# C-04_CPU_PERI1.net
KiCad netlist of a schematic drawn in Altium Designer
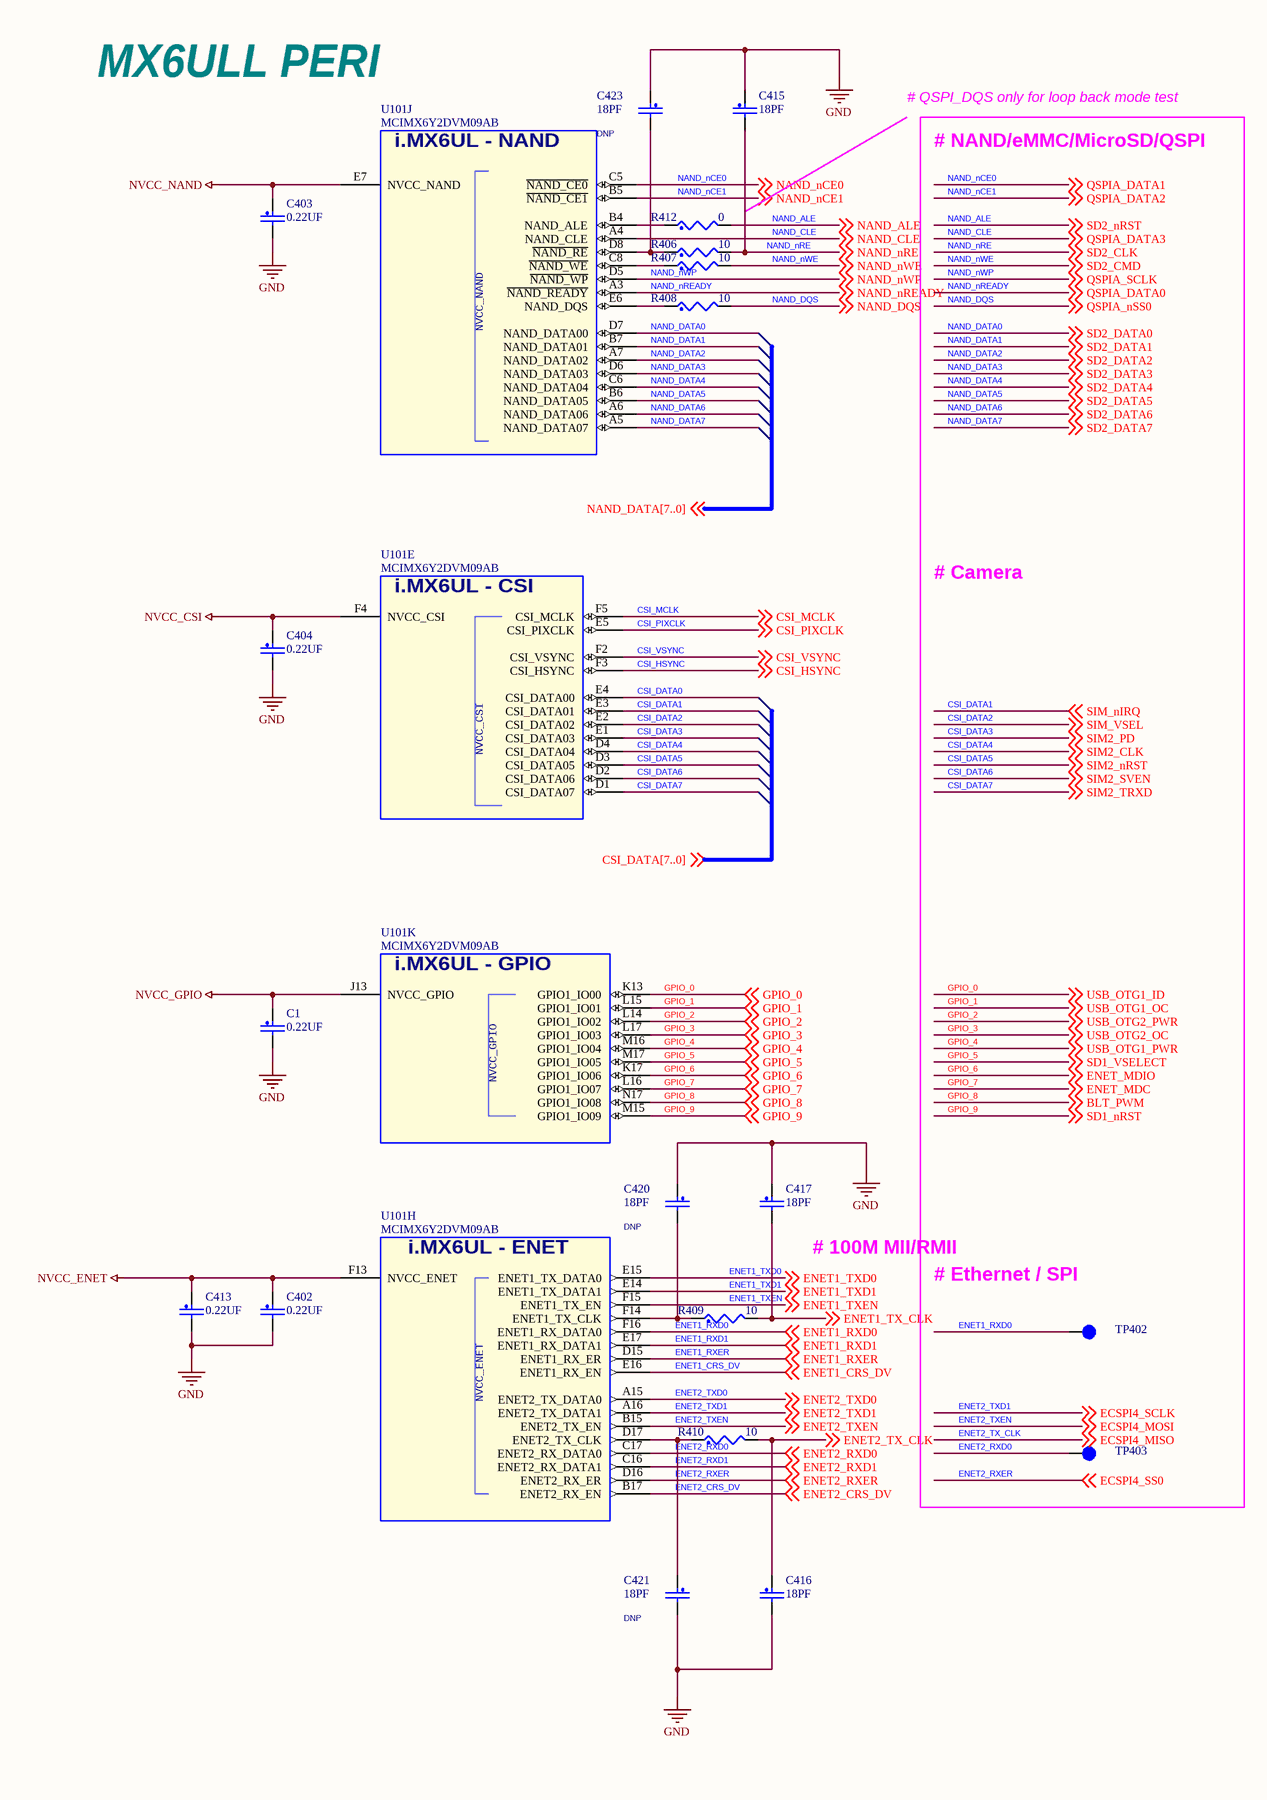
[diagram p0: C-04 CPU PERI1.SchDoc, left]
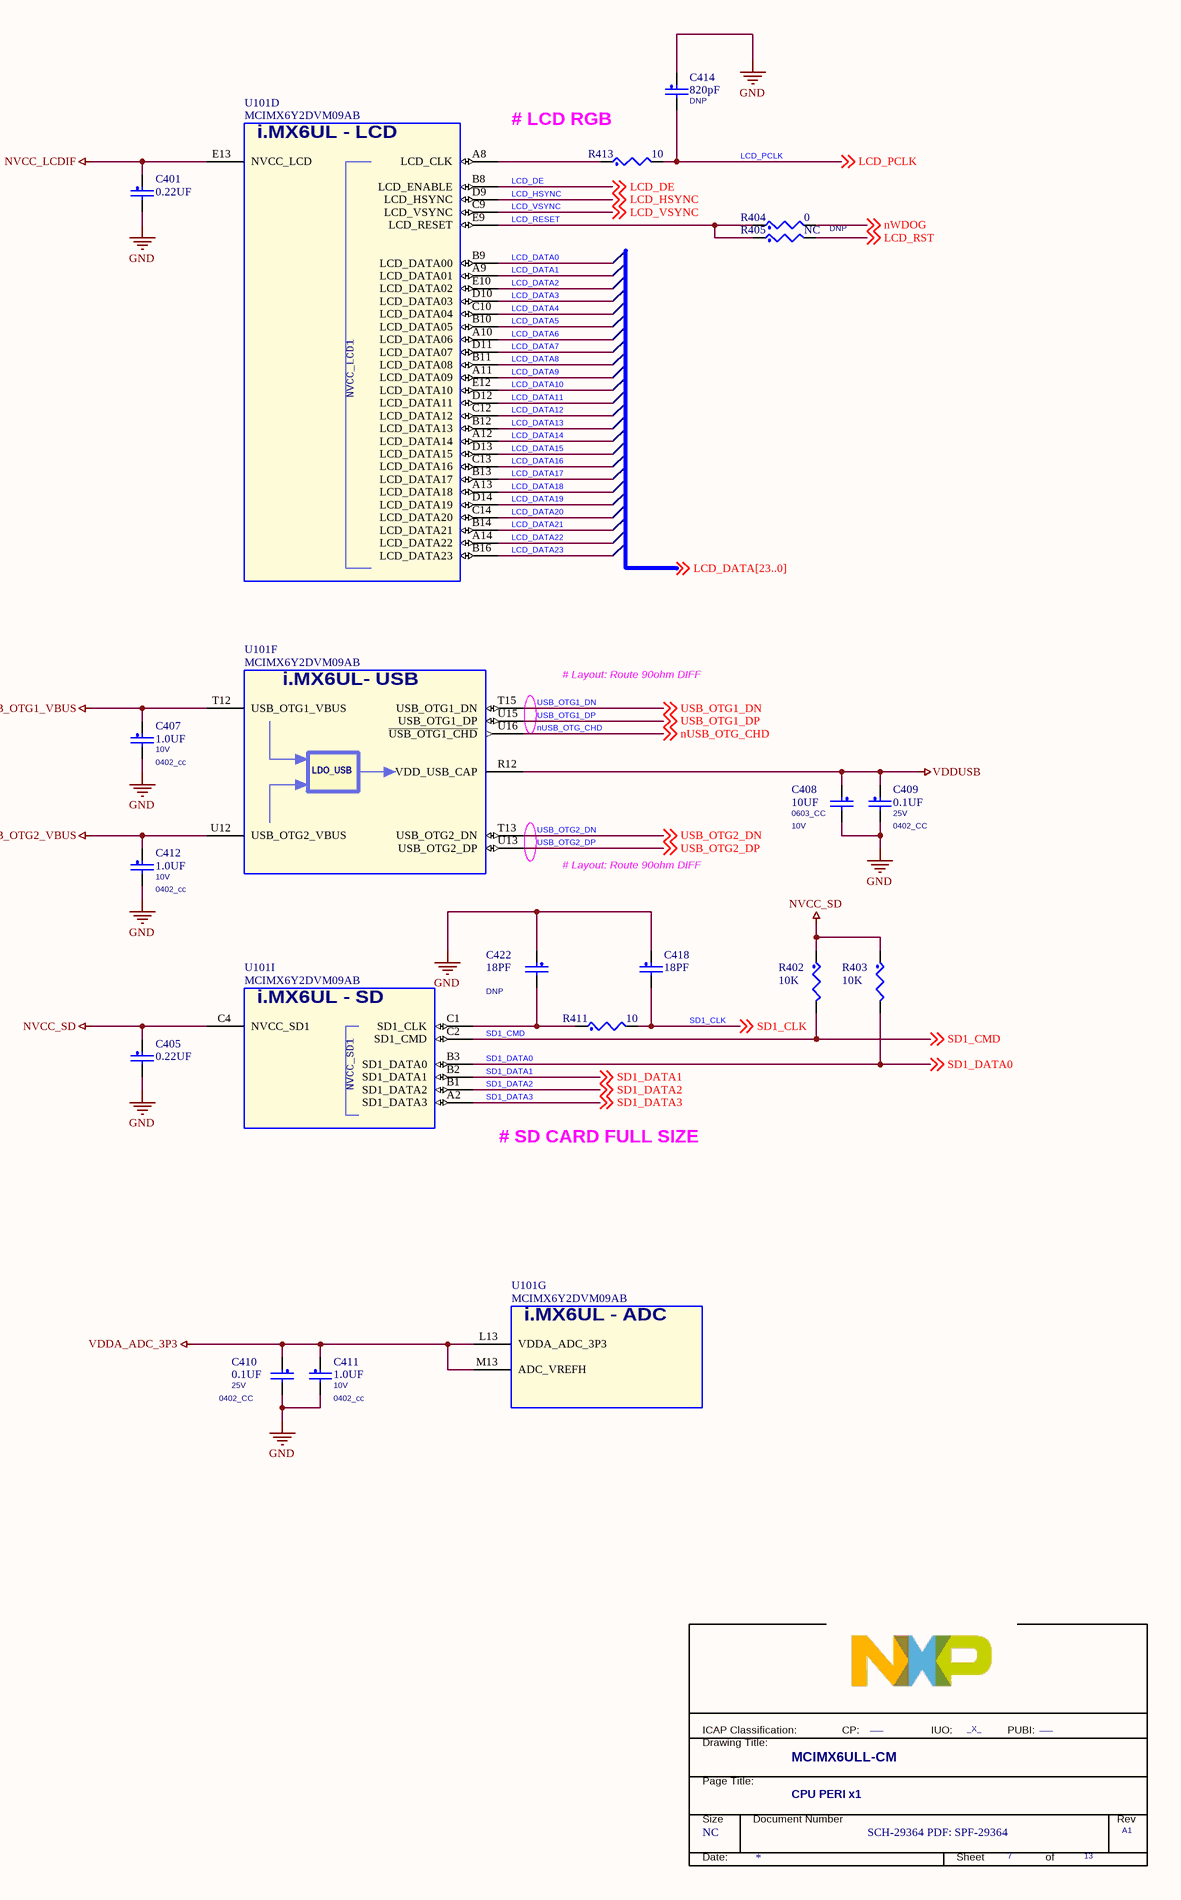
[diagram p1: C-04 CPU PERI1.SchDoc, right]

(export (version "E")
  (design (tool "Eeschema 10.0.6"))
  (components
    (comp (ref "*")
      (value "TitleBlock_FS")
      (fields
        (field (name "PAGETITLE") "CPU PERI x1")
        (field (name "PAGE COUNT") "13")
        (field (name "PAGE NUMBER") "7")
        (field (name "PAGE SIZE") "NC")
        (field (name "TITLE") "MCIMX6ULL-CM")
        (field (name "REVCODE") "A1")
        (field (name "DOC") "SCH-29364 PDF: SPF-29364")
        (field (name "FCP") "___")
        (field (name "PUBI") "___")
        (field (name "FIUO") "_X_")
      )
      (libsource (lib "*") (part "TitleBlock_FS"))
    )
    (comp (ref "C1")
      (value "0.22UF")
      (footprint "0402T_C")
      (description "CAP CER 0.22UF 10V 10% X5R 0402")
      (fields (field (name "VOLTAGE") "10V") (field (name "TOLERANCE") "10%"))
      (libsource (lib "*") (part "CAP_NP"))
    )
    (comp (ref "C401")
      (value "0.22UF")
      (footprint "0402T_C")
      (description "CAP CER 0.22UF 10V 10% X5R 0402")
      (fields (field (name "VOLTAGE") "10V") (field (name "TOLERANCE") "10%"))
      (libsource (lib "*") (part "CAP_NP"))
    )
    (comp (ref "C402")
      (value "0.22UF")
      (footprint "0402T_C")
      (description "CAP CER 0.22UF 10V 10% X5R 0402")
      (fields (field (name "VOLTAGE") "10V") (field (name "TOLERANCE") "10%"))
      (libsource (lib "*") (part "CAP_NP"))
    )
    (comp (ref "C403")
      (value "0.22UF")
      (footprint "0402T_C")
      (description "CAP CER 0.22UF 10V 10% X5R 0402")
      (fields (field (name "VOLTAGE") "10V") (field (name "TOLERANCE") "10%"))
      (libsource (lib "*") (part "CAP_NP"))
    )
    (comp (ref "C404")
      (value "0.22UF")
      (footprint "0402T_C")
      (description "CAP CER 0.22UF 10V 10% X5R 0402")
      (fields (field (name "TOLERANCE") "10%") (field (name "VOLTAGE") "10V"))
      (libsource (lib "*") (part "CAP_NP"))
    )
    (comp (ref "C405")
      (value "0.22UF")
      (footprint "0402T_C")
      (description "CAP CER 0.22UF 10V 10% X5R 0402")
      (fields (field (name "TOLERANCE") "10%") (field (name "VOLTAGE") "10V"))
      (libsource (lib "*") (part "CAP_NP"))
    )
    (comp (ref "C407")
      (value "1.0UF")
      (footprint "0402T_C")
      (description "CAP CER 1.0UF 10V 10% X5R 0402")
      (fields (field (name "VOLTAGE") "10V") (field (name "PCB FOOTPRINT") "0402_cc"))
      (libsource (lib "*") (part "CAP_NP"))
    )
    (comp (ref "C408")
      (value "10UF")
      (footprint "0402T_C")
      (description "CAP CER 10UF 10V 20% X5R 0603")
      (fields (field (name "VOLTAGE") "10V") (field (name "PCB FOOTPRINT") "0603_CC"))
      (libsource (lib "*") (part "CAP_NP"))
    )
    (comp (ref "C409")
      (value "0.1UF")
      (footprint "0402T_C")
      (description "CAP CER 0.1UF 25V 10% X5R 0402")
      (fields
        (field (name "VOLTAGE") "25V")
        (field (name "TOLERANCE") "10%")
        (field (name "PCB FOOTPRINT") "0402_CC")
      )
      (libsource (lib "*") (part "CAP_NP"))
    )
    (comp (ref "C410")
      (value "0.1UF")
      (footprint "0402T_C")
      (description "CAP CER 0.1UF 25V 10% X5R 0402")
      (fields
        (field (name "TOLERANCE") "10%")
        (field (name "VOLTAGE") "25V")
        (field (name "PCB FOOTPRINT") "0402_CC")
      )
      (libsource (lib "*") (part "CAP_NP"))
    )
    (comp (ref "C411")
      (value "1.0UF")
      (footprint "0402T_C")
      (description "CAP CER 1.0UF 10V 10% X5R 0402")
      (fields (field (name "VOLTAGE") "10V") (field (name "PCB FOOTPRINT") "0402_cc"))
      (libsource (lib "*") (part "CAP_NP"))
    )
    (comp (ref "C412")
      (value "1.0UF")
      (footprint "0402T_C")
      (description "CAP CER 1.0UF 10V 10% X5R 0402")
      (fields (field (name "VOLTAGE") "10V") (field (name "PCB FOOTPRINT") "0402_cc"))
      (libsource (lib "*") (part "CAP_NP"))
    )
    (comp (ref "C413")
      (value "0.22UF")
      (footprint "0402T_C")
      (description "CAP CER 0.22UF 10V 10% X5R 0402")
      (fields (field (name "VOLTAGE") "10V") (field (name "TOLERANCE") "10%"))
      (libsource (lib "*") (part "CAP_NP"))
    )
    (comp (ref "C414")
      (value "820pF")
      (footprint "0402T_C")
      (description "CAP CER 820PF 50V 5% X7R 0402")
      (fields (field (name "ASSY_OPT") "DNP") (field (name "TOLERANCE") "5%") (field (name "VOLTAGE") "50 V"))
      (libsource (lib "*") (part "CAP_NP"))
    )
    (comp (ref "C415")
      (value "18PF")
      (footprint "0402T_C")
      (description "CAP CER 18PF 50V 1% C0G 0402")
      (fields (field (name "VOLTAGE") "50V") (field (name "TOLERANCE") "1%"))
      (libsource (lib "*") (part "CAP_NP"))
    )
    (comp (ref "C416")
      (value "18PF")
      (footprint "0402T_C")
      (description "CAP CER 18PF 50V 1% C0G 0402")
      (fields (field (name "VOLTAGE") "50V") (field (name "TOLERANCE") "1%"))
      (libsource (lib "*") (part "CAP_NP"))
    )
    (comp (ref "C417")
      (value "18PF")
      (footprint "0402T_C")
      (description "CAP CER 18PF 50V 1% C0G 0402")
      (fields (field (name "VOLTAGE") "50V") (field (name "TOLERANCE") "1%"))
      (libsource (lib "*") (part "CAP_NP"))
    )
    (comp (ref "C418")
      (value "18PF")
      (footprint "0402T_C")
      (description "CAP CER 18PF 50V 1% C0G 0402")
      (fields (field (name "VOLTAGE") "50V") (field (name "TOLERANCE") "1%"))
      (libsource (lib "*") (part "CAP_NP"))
    )
    (comp (ref "C420")
      (value "18PF")
      (footprint "0402T_C")
      (description "CAP CER 18PF 50V 1% C0G 0402")
      (fields (field (name "ASSY_OPT") "DNP") (field (name "VOLTAGE") "50V") (field (name "TOLERANCE") "1%"))
      (libsource (lib "*") (part "CAP_NP"))
    )
    (comp (ref "C421")
      (value "18PF")
      (footprint "0402T_C")
      (description "CAP CER 18PF 50V 1% C0G 0402")
      (fields (field (name "ASSY_OPT") "DNP") (field (name "VOLTAGE") "50V") (field (name "TOLERANCE") "1%"))
      (libsource (lib "*") (part "CAP_NP"))
    )
    (comp (ref "C422")
      (value "18PF")
      (footprint "0402T_C")
      (description "CAP CER 18PF 50V 1% C0G 0402")
      (fields (field (name "ASSY_OPT") "DNP") (field (name "VOLTAGE") "50V") (field (name "TOLERANCE") "1%"))
      (libsource (lib "*") (part "CAP_NP"))
    )
    (comp (ref "C423")
      (value "18PF")
      (footprint "0402T_C")
      (description "CAP CER 18PF 50V 1% C0G 0402")
      (fields (field (name "ASSY_OPT") "DNP") (field (name "VOLTAGE") "50V") (field (name "TOLERANCE") "1%"))
      (libsource (lib "*") (part "CAP_NP"))
    )
    (comp (ref "R402")
      (value "10K")
      (footprint "0402T_C")
      (description "RES MF 10K 1/16W 5% 0402")
      (fields (field (name "TOLERANCE") "5%"))
      (libsource (lib "*") (part "RES"))
    )
    (comp (ref "R403")
      (value "10K")
      (footprint "0402T_C")
      (description "RES MF 10K 1/16W 5% 0402")
      (fields (field (name "TOLERANCE") "5%"))
      (libsource (lib "*") (part "RES"))
    )
    (comp (ref "R404")
      (value "0")
      (footprint "0603_CC")
      (description "RES MF ZERO OHM 1/16W 5% 0402")
      (fields (field (name "TOLERANCE") "5%"))
      (libsource (lib "*") (part "RES"))
    )
    (comp (ref "R405")
      (value "NC")
      (footprint "0402T_C")
      (description "RES MF ZERO OHM 1/16W 5% 0402")
      (fields (field (name "ASSY_OPT") "DNP") (field (name "TOLERANCE") "5%"))
      (libsource (lib "*") (part "RES"))
    )
    (comp (ref "R406")
      (value "10")
      (footprint "0402T_C")
      (description "RES MF 10 OHM 1/16W 5% 0402")
      (fields (field (name "TOLERANCE") "5%"))
      (libsource (lib "*") (part "RES"))
    )
    (comp (ref "R407")
      (value "10")
      (footprint "0402T_C")
      (description "RES MF 10 OHM 1/16W 5% 0402")
      (fields (field (name "TOLERANCE") "5%"))
      (libsource (lib "*") (part "RES"))
    )
    (comp (ref "R408")
      (value "10")
      (footprint "0402T_C")
      (description "RES MF 10 OHM 1/16W 5% 0402")
      (fields (field (name "TOLERANCE") "5%"))
      (libsource (lib "*") (part "RES"))
    )
    (comp (ref "R409")
      (value "10")
      (footprint "0402T_C")
      (description "RES MF 10 OHM 1/16W 5% 0402")
      (fields (field (name "TOLERANCE") "5%"))
      (libsource (lib "*") (part "RES"))
    )
    (comp (ref "R410")
      (value "10")
      (footprint "0402T_C")
      (description "RES MF 10 OHM 1/16W 5% 0402")
      (fields (field (name "TOLERANCE") "5%"))
      (libsource (lib "*") (part "RES"))
    )
    (comp (ref "R411")
      (value "10")
      (footprint "0402T_C")
      (description "RES MF 10 OHM 1/16W 5% 0402")
      (fields (field (name "TOLERANCE") "5%"))
      (libsource (lib "*") (part "RES"))
    )
    (comp (ref "R412")
      (value "0")
      (footprint "0402T_C")
      (description "RES MF ZERO OHM 1/16W 5% 0402")
      (fields (field (name "TOLERANCE") "5%"))
      (libsource (lib "*") (part "RES"))
    )
    (comp (ref "R413")
      (value "10")
      (footprint "0402T_C")
      (description "RES MF 10 OHM 1/16W 5% 0402")
      (fields (field (name "TOLERANCE") "5%"))
      (libsource (lib "*") (part "RES"))
    )
    (comp (ref "TP402")
      (value "TPAD_015")
      (footprint "TPAD_015")
      (description "TEST POINT PAD 15MIL DIA SMT, NO PART TO ORDER")
      (libsource (lib "*") (part "TESTLOOP"))
    )
    (comp (ref "TP403")
      (value "TPAD_015")
      (footprint "TPAD_015")
      (description "TEST POINT PAD 15MIL DIA SMT, NO PART TO ORDER")
      (libsource (lib "*") (part "TESTLOOP"))
    )
    (comp (ref "U101")
      (value "MCIMX6Y2DVM09AB")
      (footprint "BGA289_0P8_14X14")
      (description "IC CPU ARM COREA7 900MHZ 16BIT 3-3.6V PBGA289")
      (libsource (lib "*") (part "MCIMX6Y2DVM05AA_PBGA_289P"))
    )
  )
  (nets
    (net (code "1") (name "/LCD_RESET") (class "Default")
      (node (ref "R404") (pin "1") (pinfunction "1_1") (pintype "passive"))
      (node (ref "R405") (pin "1") (pinfunction "1_1") (pintype "passive"))
      (node (ref "U101") (pin "E9") (pinfunction "LCD_RESET_E9") (pintype "bidirectional"))
    )
    (net (code "2") (name "BLT_PWM") (class "Default")
      (node (ref "U101") (pin "N17") (pinfunction "GPIO1_IO08_N17") (pintype "bidirectional"))
    )
    (net (code "3") (name "CSI_DATA0") (class "Default")
      (node (ref "U101") (pin "E4") (pinfunction "CSI_DATA00_E4") (pintype "bidirectional"))
    )
    (net (code "5") (name "CSI_HSYNC") (class "Default")
      (node (ref "U101") (pin "F3") (pinfunction "CSI_HSYNC_F3") (pintype "bidirectional"))
    )
    (net (code "6") (name "CSI_MCLK") (class "Default")
      (node (ref "U101") (pin "F5") (pinfunction "CSI_MCLK_F5") (pintype "bidirectional"))
    )
    (net (code "7") (name "CSI_PIXCLK") (class "Default")
      (node (ref "U101") (pin "E5") (pinfunction "CSI_PIXCLK_E5") (pintype "bidirectional"))
    )
    (net (code "8") (name "CSI_VSYNC") (class "Default")
      (node (ref "U101") (pin "F2") (pinfunction "CSI_VSYNC_F2") (pintype "bidirectional"))
    )
    (net (code "9") (name "ECSPI4_MISO") (class "Default")
      (node (ref "C416") (pin "1") (pinfunction "1_1") (pintype "passive"))
      (node (ref "R410") (pin "2") (pinfunction "2_2") (pintype "passive"))
    )
    (net (code "10") (name "ECSPI4_MOSI") (class "Default")
      (node (ref "U101") (pin "B15") (pinfunction "ENET2_TX_EN_B15") (pintype "output"))
    )
    (net (code "11") (name "ECSPI4_SCLK") (class "Default")
      (node (ref "U101") (pin "A16") (pinfunction "ENET2_TX_DATA1_A16") (pintype "output"))
    )
    (net (code "12") (name "ECSPI4_SS0") (class "Default")
      (node (ref "U101") (pin "D16") (pinfunction "ENET2_RX_ER_D16") (pintype "output"))
    )
    (net (code "13") (name "ENET1_CRS_DV") (class "Default")
      (node (ref "U101") (pin "E16") (pinfunction "ENET1_RX_EN_E16") (pintype "output"))
    )
    (net (code "14") (name "ENET1_RXD0") (class "Default")
      (node (ref "TP402") (pin "1") (pinfunction "Pin1_1") (pintype "passive"))
      (node (ref "U101") (pin "F16") (pinfunction "ENET1_RX_DATA0_F16") (pintype "output"))
    )
    (net (code "15") (name "ENET1_RXD1") (class "Default")
      (node (ref "U101") (pin "E17") (pinfunction "ENET1_RX_DATA1_E17") (pintype "output"))
    )
    (net (code "16") (name "ENET1_RXER") (class "Default")
      (node (ref "U101") (pin "D15") (pinfunction "ENET1_RX_ER_D15") (pintype "output"))
    )
    (net (code "17") (name "ENET1_TXD0") (class "Default")
      (node (ref "U101") (pin "E15") (pinfunction "ENET1_TX_DATA0_E15") (pintype "output"))
    )
    (net (code "18") (name "ENET1_TXD1") (class "Default")
      (node (ref "U101") (pin "E14") (pinfunction "ENET1_TX_DATA1_E14") (pintype "output"))
    )
    (net (code "19") (name "ENET1_TXEN") (class "Default")
      (node (ref "U101") (pin "F15") (pinfunction "ENET1_TX_EN_F15") (pintype "output"))
    )
    (net (code "20") (name "ENET1_TX_CLK") (class "Default")
      (node (ref "C417") (pin "2") (pinfunction "2_2") (pintype "passive"))
      (node (ref "R409") (pin "2") (pinfunction "2_2") (pintype "passive"))
    )
    (net (code "21") (name "ENET2_CRS_DV") (class "Default")
      (node (ref "U101") (pin "B17") (pinfunction "ENET2_RX_EN_B17") (pintype "output"))
    )
    (net (code "22") (name "ENET2_RXD0") (class "Default")
      (node (ref "TP403") (pin "1") (pinfunction "Pin1_1") (pintype "passive"))
      (node (ref "U101") (pin "C17") (pinfunction "ENET2_RX_DATA0_C17") (pintype "output"))
    )
    (net (code "23") (name "ENET2_RXD1") (class "Default")
      (node (ref "U101") (pin "C16") (pinfunction "ENET2_RX_DATA1_C16") (pintype "output"))
    )
    (net (code "24") (name "ENET2_TXD0") (class "Default")
      (node (ref "U101") (pin "A15") (pinfunction "ENET2_TX_DATA0_A15") (pintype "output"))
    )
    (net (code "25") (name "ENET_MDC") (class "Default")
      (node (ref "U101") (pin "L16") (pinfunction "GPIO1_IO07_L16") (pintype "bidirectional"))
    )
    (net (code "26") (name "ENET_MDIO") (class "Default")
      (node (ref "U101") (pin "K17") (pinfunction "GPIO1_IO06_K17") (pintype "bidirectional"))
    )
    (net (code "27") (name "GND") (class "Default")
      (node (ref "C1") (pin "2") (pinfunction "2_2") (pintype "passive"))
      (node (ref "C401") (pin "2") (pinfunction "2_2") (pintype "passive"))
      (node (ref "C402") (pin "2") (pinfunction "2_2") (pintype "passive"))
      (node (ref "C403") (pin "2") (pinfunction "2_2") (pintype "passive"))
      (node (ref "C404") (pin "2") (pinfunction "2_2") (pintype "passive"))
      (node (ref "C405") (pin "2") (pinfunction "2_2") (pintype "passive"))
      (node (ref "C407") (pin "2") (pinfunction "2_2") (pintype "passive"))
      (node (ref "C408") (pin "2") (pinfunction "2_2") (pintype "passive"))
      (node (ref "C409") (pin "2") (pinfunction "2_2") (pintype "passive"))
      (node (ref "C410") (pin "2") (pinfunction "2_2") (pintype "passive"))
      (node (ref "C411") (pin "2") (pinfunction "2_2") (pintype "passive"))
      (node (ref "C412") (pin "2") (pinfunction "2_2") (pintype "passive"))
      (node (ref "C413") (pin "2") (pinfunction "2_2") (pintype "passive"))
      (node (ref "C414") (pin "1") (pinfunction "1_1") (pintype "passive"))
      (node (ref "C415") (pin "1") (pinfunction "1_1") (pintype "passive"))
      (node (ref "C416") (pin "2") (pinfunction "2_2") (pintype "passive"))
      (node (ref "C417") (pin "1") (pinfunction "1_1") (pintype "passive"))
      (node (ref "C418") (pin "1") (pinfunction "1_1") (pintype "passive"))
      (node (ref "C420") (pin "1") (pinfunction "1_1") (pintype "passive"))
      (node (ref "C421") (pin "2") (pinfunction "2_2") (pintype "passive"))
      (node (ref "C422") (pin "1") (pinfunction "1_1") (pintype "passive"))
      (node (ref "C423") (pin "1") (pinfunction "1_1") (pintype "passive"))
    )
    (net (code "28") (name "GPIO_0") (class "Default")
      (node (ref "U101") (pin "K13") (pinfunction "GPIO1_IO00_K13") (pintype "bidirectional"))
    )
    (net (code "29") (name "GPIO_1") (class "Default")
      (node (ref "U101") (pin "L15") (pinfunction "GPIO1_IO01_L15") (pintype "bidirectional"))
    )
    (net (code "30") (name "GPIO_2") (class "Default")
      (node (ref "U101") (pin "L14") (pinfunction "GPIO1_IO02_L14") (pintype "bidirectional"))
    )
    (net (code "31") (name "GPIO_3") (class "Default")
      (node (ref "U101") (pin "L17") (pinfunction "GPIO1_IO03_L17") (pintype "bidirectional"))
    )
    (net (code "32") (name "GPIO_4") (class "Default")
      (node (ref "U101") (pin "M16") (pinfunction "GPIO1_IO04_M16") (pintype "bidirectional"))
    )
    (net (code "33") (name "GPIO_5") (class "Default")
      (node (ref "U101") (pin "M17") (pinfunction "GPIO1_IO05_M17") (pintype "bidirectional"))
    )
    (net (code "34") (name "GPIO_9") (class "Default")
      (node (ref "U101") (pin "M15") (pinfunction "GPIO1_IO09_M15") (pintype "bidirectional"))
    )
    (net (code "35") (name "LCD_DATA0") (class "Default")
      (node (ref "U101") (pin "B9") (pinfunction "LCD_DATA00_B9") (pintype "bidirectional"))
    )
    (net (code "36") (name "LCD_DATA1") (class "Default")
      (node (ref "U101") (pin "A9") (pinfunction "LCD_DATA01_A9") (pintype "bidirectional"))
    )
    (net (code "37") (name "LCD_DATA2") (class "Default")
      (node (ref "U101") (pin "E10") (pinfunction "LCD_DATA02_E10") (pintype "bidirectional"))
    )
    (net (code "38") (name "LCD_DATA3") (class "Default")
      (node (ref "U101") (pin "D10") (pinfunction "LCD_DATA03_D10") (pintype "bidirectional"))
    )
    (net (code "39") (name "LCD_DATA4") (class "Default")
      (node (ref "U101") (pin "C10") (pinfunction "LCD_DATA04_C10") (pintype "bidirectional"))
    )
    (net (code "40") (name "LCD_DATA5") (class "Default")
      (node (ref "U101") (pin "B10") (pinfunction "LCD_DATA05_B10") (pintype "bidirectional"))
    )
    (net (code "41") (name "LCD_DATA6") (class "Default")
      (node (ref "U101") (pin "A10") (pinfunction "LCD_DATA06_A10") (pintype "bidirectional"))
    )
    (net (code "42") (name "LCD_DATA7") (class "Default")
      (node (ref "U101") (pin "D11") (pinfunction "LCD_DATA07_D11") (pintype "bidirectional"))
    )
    (net (code "43") (name "LCD_DATA8") (class "Default")
      (node (ref "U101") (pin "B11") (pinfunction "LCD_DATA08_B11") (pintype "bidirectional"))
    )
    (net (code "44") (name "LCD_DATA9") (class "Default")
      (node (ref "U101") (pin "A11") (pinfunction "LCD_DATA09_A11") (pintype "bidirectional"))
    )
    (net (code "45") (name "LCD_DATA10") (class "Default")
      (node (ref "U101") (pin "E12") (pinfunction "LCD_DATA10_E12") (pintype "bidirectional"))
    )
    (net (code "46") (name "LCD_DATA11") (class "Default")
      (node (ref "U101") (pin "D12") (pinfunction "LCD_DATA11_D12") (pintype "bidirectional"))
    )
    (net (code "47") (name "LCD_DATA12") (class "Default")
      (node (ref "U101") (pin "C12") (pinfunction "LCD_DATA12_C12") (pintype "bidirectional"))
    )
    (net (code "48") (name "LCD_DATA13") (class "Default")
      (node (ref "U101") (pin "B12") (pinfunction "LCD_DATA13_B12") (pintype "bidirectional"))
    )
    (net (code "49") (name "LCD_DATA14") (class "Default")
      (node (ref "U101") (pin "A12") (pinfunction "LCD_DATA14_A12") (pintype "bidirectional"))
    )
    (net (code "50") (name "LCD_DATA15") (class "Default")
      (node (ref "U101") (pin "D13") (pinfunction "LCD_DATA15_D13") (pintype "bidirectional"))
    )
    (net (code "51") (name "LCD_DATA16") (class "Default")
      (node (ref "U101") (pin "C13") (pinfunction "LCD_DATA16_C13") (pintype "bidirectional"))
    )
    (net (code "52") (name "LCD_DATA17") (class "Default")
      (node (ref "U101") (pin "B13") (pinfunction "LCD_DATA17_B13") (pintype "bidirectional"))
    )
    (net (code "53") (name "LCD_DATA18") (class "Default")
      (node (ref "U101") (pin "A13") (pinfunction "LCD_DATA18_A13") (pintype "bidirectional"))
    )
    (net (code "54") (name "LCD_DATA19") (class "Default")
      (node (ref "U101") (pin "D14") (pinfunction "LCD_DATA19_D14") (pintype "bidirectional"))
    )
    (net (code "55") (name "LCD_DATA20") (class "Default")
      (node (ref "U101") (pin "C14") (pinfunction "LCD_DATA20_C14") (pintype "bidirectional"))
    )
    (net (code "56") (name "LCD_DATA21") (class "Default")
      (node (ref "U101") (pin "B14") (pinfunction "LCD_DATA21_B14") (pintype "bidirectional"))
    )
    (net (code "57") (name "LCD_DATA22") (class "Default")
      (node (ref "U101") (pin "A14") (pinfunction "LCD_DATA22_A14") (pintype "bidirectional"))
    )
    (net (code "58") (name "LCD_DATA23") (class "Default")
      (node (ref "U101") (pin "B16") (pinfunction "LCD_DATA23_B16") (pintype "bidirectional"))
    )
    (net (code "60") (name "LCD_DE") (class "Default")
      (node (ref "U101") (pin "B8") (pinfunction "LCD_ENABLE_B8") (pintype "bidirectional"))
    )
    (net (code "61") (name "LCD_HSYNC") (class "Default")
      (node (ref "U101") (pin "D9") (pinfunction "LCD_HSYNC_D9") (pintype "bidirectional"))
    )
    (net (code "62") (name "LCD_PCLK") (class "Default")
      (node (ref "C414") (pin "2") (pinfunction "2_2") (pintype "passive"))
      (node (ref "R413") (pin "2") (pinfunction "2_2") (pintype "passive"))
    )
    (net (code "63") (name "LCD_RST") (class "Default")
      (node (ref "R405") (pin "2") (pinfunction "2_2") (pintype "passive"))
    )
    (net (code "64") (name "LCD_VSYNC") (class "Default")
      (node (ref "U101") (pin "C9") (pinfunction "LCD_VSYNC_C9") (pintype "bidirectional"))
    )
    (net (code "65") (name "NAND_ALE") (class "Default")
      (node (ref "R412") (pin "2") (pinfunction "2_2") (pintype "passive"))
    )
    (net (code "66") (name "NAND_CLE") (class "Default")
      (node (ref "U101") (pin "A4") (pinfunction "NAND_CLE_A4") (pintype "bidirectional"))
    )
    (net (code "68") (name "NAND_DQS") (class "Default")
      (node (ref "R408") (pin "2") (pinfunction "2_2") (pintype "passive"))
    )
    (net (code "69") (name "NAND_nCE0") (class "Default")
      (node (ref "U101") (pin "C5") (pinfunction "~{NAND_CE0}_C5") (pintype "bidirectional"))
    )
    (net (code "70") (name "NAND_nCE1") (class "Default")
      (node (ref "U101") (pin "B5") (pinfunction "~{NAND_CE1}_B5") (pintype "bidirectional"))
    )
    (net (code "71") (name "NAND_nRE") (class "Default")
      (node (ref "C415") (pin "2") (pinfunction "2_2") (pintype "passive"))
      (node (ref "R406") (pin "2") (pinfunction "2_2") (pintype "passive"))
    )
    (net (code "72") (name "NAND_nREADY") (class "Default")
      (node (ref "U101") (pin "A3") (pinfunction "~{NAND_READY}_A3") (pintype "bidirectional"))
    )
    (net (code "73") (name "NAND_nWE") (class "Default")
      (node (ref "R407") (pin "2") (pinfunction "2_2") (pintype "passive"))
    )
    (net (code "74") (name "NAND_nWP") (class "Default")
      (node (ref "U101") (pin "D5") (pinfunction "~{NAND_WP}_D5") (pintype "bidirectional"))
    )
    (net (code "75") (name "NVCC_CSI") (class "Default")
      (node (ref "C404") (pin "1") (pinfunction "1_1") (pintype "passive"))
      (node (ref "U101") (pin "F4") (pinfunction "NVCC_CSI_F4") (pintype "power_in"))
    )
    (net (code "76") (name "NVCC_ENET") (class "Default")
      (node (ref "C402") (pin "1") (pinfunction "1_1") (pintype "passive"))
      (node (ref "C413") (pin "1") (pinfunction "1_1") (pintype "passive"))
      (node (ref "U101") (pin "F13") (pinfunction "NVCC_ENET_F13") (pintype "power_in"))
    )
    (net (code "77") (name "NVCC_GPIO") (class "Default")
      (node (ref "C1") (pin "1") (pinfunction "1_1") (pintype "passive"))
      (node (ref "U101") (pin "J13") (pinfunction "NVCC_GPIO_J13") (pintype "power_in"))
    )
    (net (code "78") (name "NVCC_LCDIF") (class "Default")
      (node (ref "C401") (pin "1") (pinfunction "1_1") (pintype "passive"))
      (node (ref "U101") (pin "E13") (pinfunction "NVCC_LCD_E13") (pintype "power_in"))
    )
    (net (code "79") (name "NVCC_NAND") (class "Default")
      (node (ref "C403") (pin "1") (pinfunction "1_1") (pintype "passive"))
      (node (ref "U101") (pin "E7") (pinfunction "NVCC_NAND_E7") (pintype "power_in"))
    )
    (net (code "80") (name "NVCC_SD") (class "Default")
      (node (ref "C405") (pin "1") (pinfunction "1_1") (pintype "passive"))
      (node (ref "R402") (pin "1") (pinfunction "1_1") (pintype "passive"))
      (node (ref "R403") (pin "1") (pinfunction "1_1") (pintype "passive"))
      (node (ref "U101") (pin "C4") (pinfunction "NVCC_SD1_C4") (pintype "power_in"))
    )
    (net (code "81") (name "Net-(U101D-LCD_CLK)") (class "Default")
      (node (ref "R413") (pin "1") (pinfunction "1_1") (pintype "passive"))
      (node (ref "U101") (pin "A8") (pinfunction "LCD_CLK_A8") (pintype "bidirectional"))
    )
    (net (code "82") (name "Net-(U101H-ENET1_TX_CLK)") (class "Default")
      (node (ref "C420") (pin "2") (pinfunction "2_2") (pintype "passive"))
      (node (ref "R409") (pin "1") (pinfunction "1_1") (pintype "passive"))
      (node (ref "U101") (pin "F14") (pinfunction "ENET1_TX_CLK_F14") (pintype "output"))
    )
    (net (code "83") (name "Net-(U101H-ENET2_TX_CLK)") (class "Default")
      (node (ref "C421") (pin "1") (pinfunction "1_1") (pintype "passive"))
      (node (ref "R410") (pin "1") (pinfunction "1_1") (pintype "passive"))
      (node (ref "U101") (pin "D17") (pinfunction "ENET2_TX_CLK_D17") (pintype "output"))
    )
    (net (code "84") (name "Net-(U101I-SD1_CLK)") (class "Default")
      (node (ref "C422") (pin "2") (pinfunction "2_2") (pintype "passive"))
      (node (ref "R411") (pin "1") (pinfunction "1_1") (pintype "passive"))
      (node (ref "U101") (pin "C1") (pinfunction "SD1_CLK_C1") (pintype "bidirectional"))
    )
    (net (code "85") (name "Net-(U101J-NAND_ALE)") (class "Default")
      (node (ref "R412") (pin "1") (pinfunction "1_1") (pintype "passive"))
      (node (ref "U101") (pin "B4") (pinfunction "NAND_ALE_B4") (pintype "bidirectional"))
    )
    (net (code "86") (name "Net-(U101J-NAND_DQS)") (class "Default")
      (node (ref "R408") (pin "1") (pinfunction "1_1") (pintype "passive"))
      (node (ref "U101") (pin "E6") (pinfunction "NAND_DQS_E6") (pintype "bidirectional"))
    )
    (net (code "87") (name "Net-(U101J-~{NAND_RE})") (class "Default")
      (node (ref "C423") (pin "2") (pinfunction "2_2") (pintype "passive"))
      (node (ref "R406") (pin "1") (pinfunction "1_1") (pintype "passive"))
      (node (ref "U101") (pin "D8") (pinfunction "~{NAND_RE}_D8") (pintype "bidirectional"))
    )
    (net (code "88") (name "Net-(U101J-~{NAND_WE})") (class "Default")
      (node (ref "R407") (pin "1") (pinfunction "1_1") (pintype "passive"))
      (node (ref "U101") (pin "C8") (pinfunction "~{NAND_WE}_C8") (pintype "bidirectional"))
    )
    (net (code "89") (name "SD1_CLK") (class "Default")
      (node (ref "C418") (pin "2") (pinfunction "2_2") (pintype "passive"))
      (node (ref "R411") (pin "2") (pinfunction "2_2") (pintype "passive"))
    )
    (net (code "90") (name "SD1_CMD") (class "Default")
      (node (ref "R402") (pin "2") (pinfunction "2_2") (pintype "passive"))
      (node (ref "U101") (pin "C2") (pinfunction "SD1_CMD_C2") (pintype "bidirectional"))
    )
    (net (code "91") (name "SD1_DATA0") (class "Default")
      (node (ref "R403") (pin "2") (pinfunction "2_2") (pintype "passive"))
      (node (ref "U101") (pin "B3") (pinfunction "SD1_DATA0_B3") (pintype "bidirectional"))
    )
    (net (code "92") (name "SD1_DATA1") (class "Default")
      (node (ref "U101") (pin "B2") (pinfunction "SD1_DATA1_B2") (pintype "bidirectional"))
    )
    (net (code "93") (name "SD1_DATA2") (class "Default")
      (node (ref "U101") (pin "B1") (pinfunction "SD1_DATA2_B1") (pintype "bidirectional"))
    )
    (net (code "94") (name "SD1_DATA3") (class "Default")
      (node (ref "U101") (pin "A2") (pinfunction "SD1_DATA3_A2") (pintype "bidirectional"))
    )
    (net (code "95") (name "SD2_DATA0") (class "Default")
      (node (ref "U101") (pin "D7") (pinfunction "NAND_DATA00_D7") (pintype "bidirectional"))
    )
    (net (code "96") (name "SD2_DATA1") (class "Default")
      (node (ref "U101") (pin "B7") (pinfunction "NAND_DATA01_B7") (pintype "bidirectional"))
    )
    (net (code "97") (name "SD2_DATA2") (class "Default")
      (node (ref "U101") (pin "A7") (pinfunction "NAND_DATA02_A7") (pintype "bidirectional"))
    )
    (net (code "98") (name "SD2_DATA3") (class "Default")
      (node (ref "U101") (pin "D6") (pinfunction "NAND_DATA03_D6") (pintype "bidirectional"))
    )
    (net (code "99") (name "SD2_DATA4") (class "Default")
      (node (ref "U101") (pin "C6") (pinfunction "NAND_DATA04_C6") (pintype "bidirectional"))
    )
    (net (code "100") (name "SD2_DATA5") (class "Default")
      (node (ref "U101") (pin "B6") (pinfunction "NAND_DATA05_B6") (pintype "bidirectional"))
    )
    (net (code "101") (name "SD2_DATA6") (class "Default")
      (node (ref "U101") (pin "A6") (pinfunction "NAND_DATA06_A6") (pintype "bidirectional"))
    )
    (net (code "102") (name "SD2_DATA7") (class "Default")
      (node (ref "U101") (pin "A5") (pinfunction "NAND_DATA07_A5") (pintype "bidirectional"))
    )
    (net (code "103") (name "SIM2_CLK") (class "Default")
      (node (ref "U101") (pin "D4") (pinfunction "CSI_DATA04_D4") (pintype "bidirectional"))
    )
    (net (code "104") (name "SIM2_PD") (class "Default")
      (node (ref "U101") (pin "E1") (pinfunction "CSI_DATA03_E1") (pintype "bidirectional"))
    )
    (net (code "105") (name "SIM2_SVEN") (class "Default")
      (node (ref "U101") (pin "D2") (pinfunction "CSI_DATA06_D2") (pintype "bidirectional"))
    )
    (net (code "106") (name "SIM2_TRXD") (class "Default")
      (node (ref "U101") (pin "D1") (pinfunction "CSI_DATA07_D1") (pintype "bidirectional"))
    )
    (net (code "107") (name "SIM2_nRST") (class "Default")
      (node (ref "U101") (pin "D3") (pinfunction "CSI_DATA05_D3") (pintype "bidirectional"))
    )
    (net (code "108") (name "SIM_VSEL") (class "Default")
      (node (ref "U101") (pin "E2") (pinfunction "CSI_DATA02_E2") (pintype "bidirectional"))
    )
    (net (code "109") (name "SIM_nIRQ") (class "Default")
      (node (ref "U101") (pin "E3") (pinfunction "CSI_DATA01_E3") (pintype "bidirectional"))
    )
    (net (code "110") (name "USB_OTG1_DN") (class "Default")
      (node (ref "U101") (pin "T15") (pinfunction "USB_OTG1_DN_T15") (pintype "bidirectional"))
    )
    (net (code "111") (name "USB_OTG1_DP") (class "Default")
      (node (ref "U101") (pin "U15") (pinfunction "USB_OTG1_DP_U15") (pintype "bidirectional"))
    )
    (net (code "112") (name "USB_OTG1_VBUS") (class "Default")
      (node (ref "C407") (pin "1") (pinfunction "1_1") (pintype "passive"))
      (node (ref "U101") (pin "T12") (pinfunction "USB_OTG1_VBUS_T12") (pintype "power_in"))
    )
    (net (code "113") (name "USB_OTG2_DN") (class "Default")
      (node (ref "U101") (pin "T13") (pinfunction "USB_OTG2_DN_T13") (pintype "bidirectional"))
    )
    (net (code "114") (name "USB_OTG2_DP") (class "Default")
      (node (ref "U101") (pin "U13") (pinfunction "USB_OTG2_DP_U13") (pintype "bidirectional"))
    )
    (net (code "115") (name "USB_OTG2_VBUS") (class "Default")
      (node (ref "C412") (pin "1") (pinfunction "1_1") (pintype "passive"))
      (node (ref "U101") (pin "U12") (pinfunction "USB_OTG2_VBUS_U12") (pintype "power_in"))
    )
    (net (code "116") (name "VDDA_ADC_3P3") (class "Default")
      (node (ref "C410") (pin "1") (pinfunction "1_1") (pintype "passive"))
      (node (ref "C411") (pin "1") (pinfunction "1_1") (pintype "passive"))
      (node (ref "U101") (pin "L13") (pinfunction "VDDA_ADC_3P3_L13") (pintype "power_in"))
      (node (ref "U101") (pin "M13") (pinfunction "ADC_VREFH_M13") (pintype "power_in"))
    )
    (net (code "117") (name "VDDUSB") (class "Default")
      (node (ref "C408") (pin "1") (pinfunction "1_1") (pintype "passive"))
      (node (ref "C409") (pin "1") (pinfunction "1_1") (pintype "passive"))
      (node (ref "U101") (pin "R12") (pinfunction "VDD_USB_CAP_R12") (pintype "power_in"))
    )
    (net (code "118") (name "nUSB_OTG_CHD") (class "Default")
      (node (ref "U101") (pin "U16") (pinfunction "~{USB_OTG1_CHD}_U16") (pintype "output"))
    )
    (net (code "119") (name "nWDOG") (class "Default")
      (node (ref "R404") (pin "2") (pinfunction "2_2") (pintype "passive"))
    )
  )
)
